# satshakit-M7.net
KiCad netlist of a schematic drawn in EAGLE
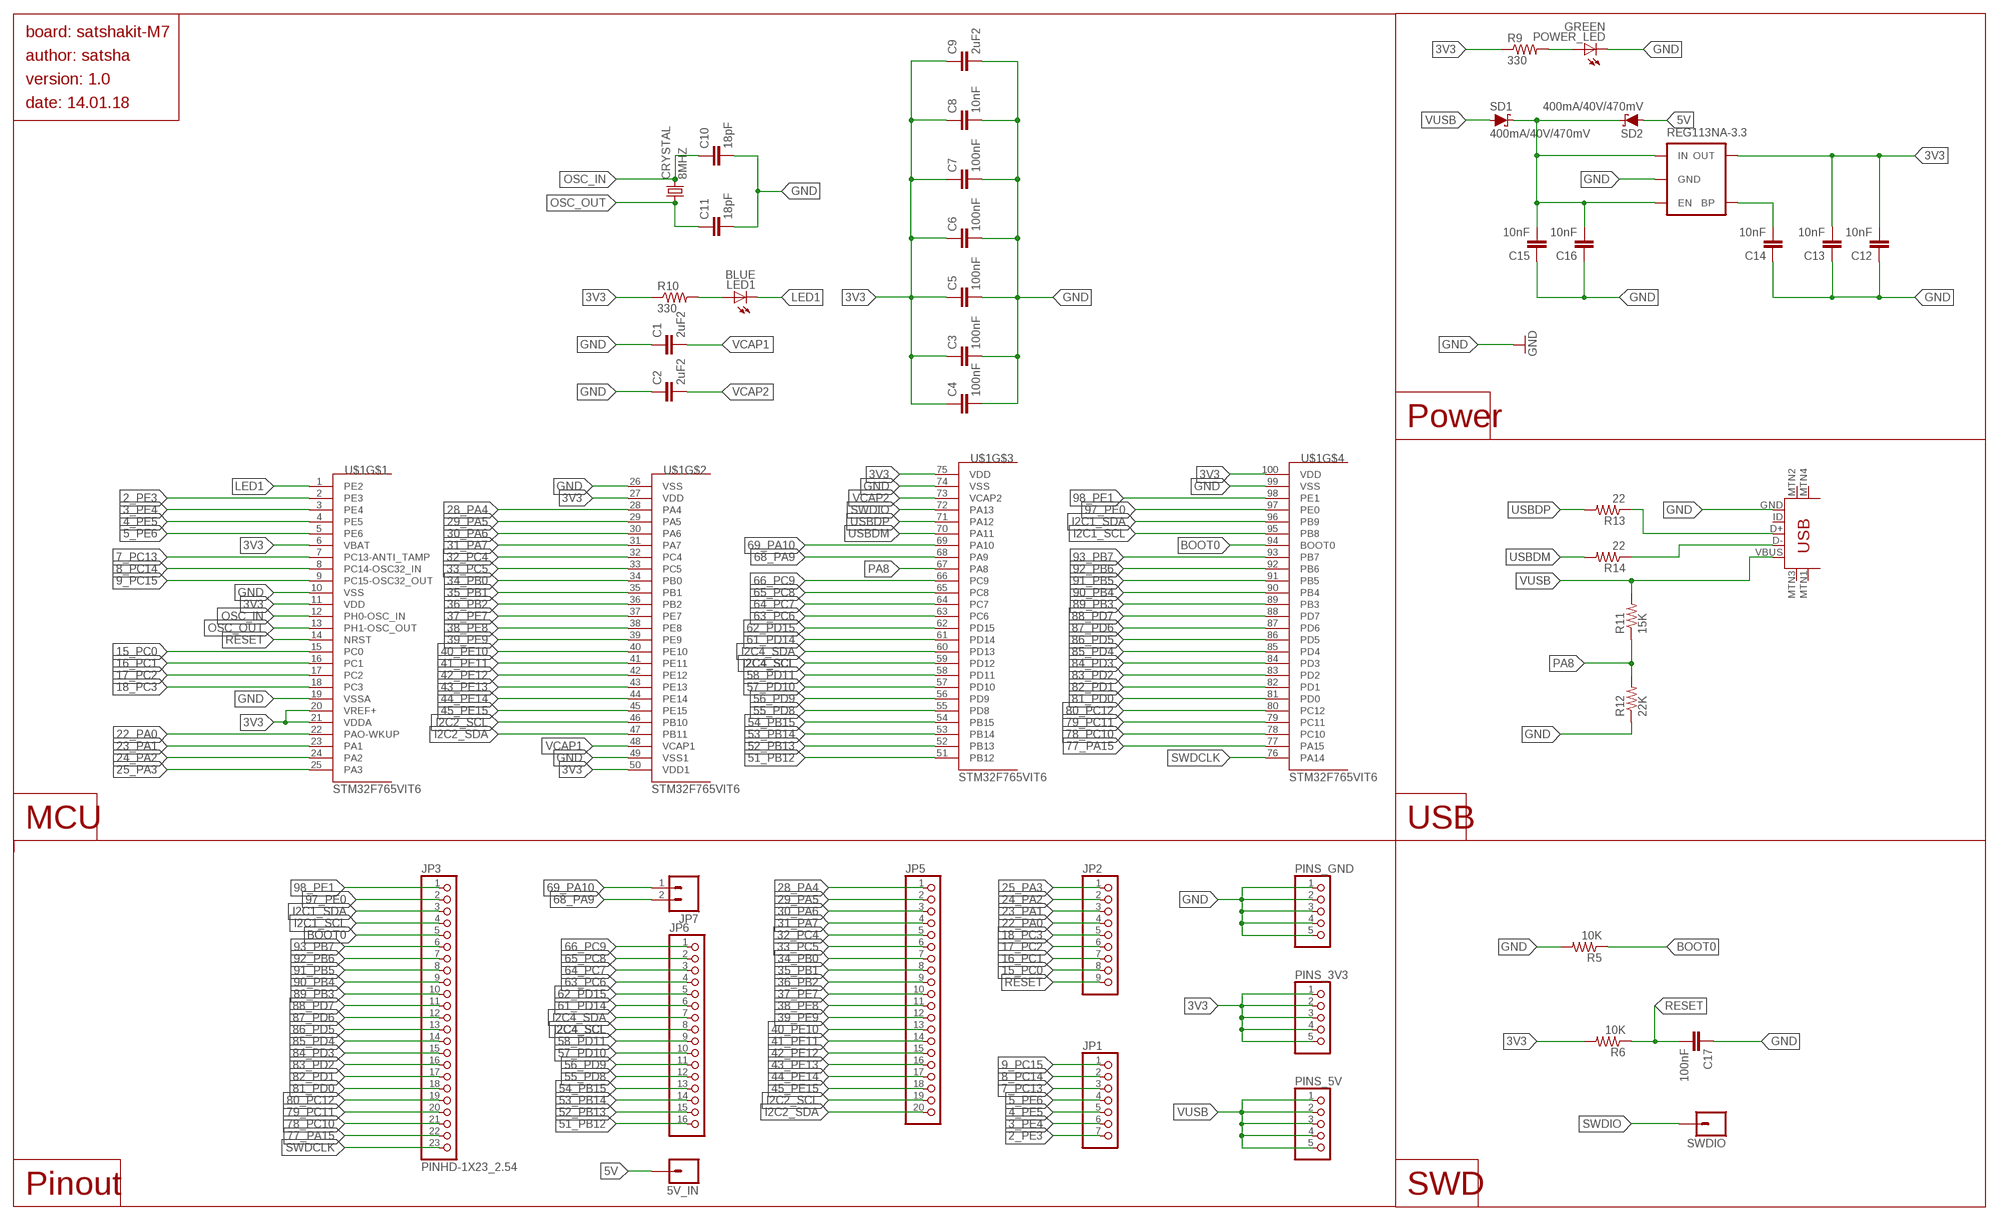
[diagram p0: schematic, sheet 1]

(export (version "E")
  (design (tool "Eeschema 10.0.6"))
  (components
    (comp (ref "5V_IN")
      (value "M01PTH_LONGPAD")
      (footprint "eagle-import:1X01_LONGPAD")
      (libsource (lib "eagle-import") (part "M01PTH_LONGPAD"))
    )
    (comp (ref "C1")
      (value "2uF2")
      (footprint "eagle-import:1206")
      (libsource (lib "eagle-import") (part "CAP1206"))
    )
    (comp (ref "C2")
      (value "2uF2")
      (footprint "eagle-import:1206")
      (libsource (lib "eagle-import") (part "CAP1206"))
    )
    (comp (ref "C3")
      (value "100nF")
      (footprint "eagle-import:1206")
      (libsource (lib "eagle-import") (part "CAP1206"))
    )
    (comp (ref "C4")
      (value "100nF")
      (footprint "eagle-import:1206")
      (libsource (lib "eagle-import") (part "CAP1206"))
    )
    (comp (ref "C5")
      (value "100nF")
      (footprint "eagle-import:1206")
      (libsource (lib "eagle-import") (part "CAP1206"))
    )
    (comp (ref "C6")
      (value "100nF")
      (footprint "eagle-import:1206")
      (libsource (lib "eagle-import") (part "CAP1206"))
    )
    (comp (ref "C7")
      (value "100nF")
      (footprint "eagle-import:1206")
      (libsource (lib "eagle-import") (part "CAP1206"))
    )
    (comp (ref "C8")
      (value "10nF")
      (footprint "eagle-import:1206")
      (libsource (lib "eagle-import") (part "CAP1206"))
    )
    (comp (ref "C9")
      (value "2uF2")
      (footprint "eagle-import:1206")
      (libsource (lib "eagle-import") (part "CAP1206"))
    )
    (comp (ref "C10")
      (value "18pF")
      (footprint "eagle-import:1206")
      (libsource (lib "eagle-import") (part "CAP1206"))
    )
    (comp (ref "C11")
      (value "18pF")
      (footprint "eagle-import:1206")
      (libsource (lib "eagle-import") (part "CAP1206"))
    )
    (comp (ref "C12")
      (value "10nF")
      (footprint "eagle-import:1206")
      (libsource (lib "eagle-import") (part "CAP1206"))
    )
    (comp (ref "C13")
      (value "10nF")
      (footprint "eagle-import:1206")
      (libsource (lib "eagle-import") (part "CAP1206"))
    )
    (comp (ref "C14")
      (value "10nF")
      (footprint "eagle-import:1206")
      (libsource (lib "eagle-import") (part "CAP1206"))
    )
    (comp (ref "C15")
      (value "10nF")
      (footprint "eagle-import:1206")
      (libsource (lib "eagle-import") (part "CAP1206"))
    )
    (comp (ref "C16")
      (value "10nF")
      (footprint "eagle-import:1206")
      (libsource (lib "eagle-import") (part "CAP1206"))
    )
    (comp (ref "C17")
      (value "100nF")
      (footprint "eagle-import:1206")
      (libsource (lib "eagle-import") (part "CAP1206"))
    )
    (comp (ref "CRYSTAL")
      (value "8MHZ")
      (footprint "eagle-import:CSM-7X-DU")
      (libsource (lib "eagle-import") (part "CSM-7X-DU"))
    )
    (comp (ref "JP1")
      (value "PINHD-1X07_2.54")
      (footprint "eagle-import:1X07")
      (libsource (lib "eagle-import") (part "PINHD-1X07_2.54"))
    )
    (comp (ref "JP2")
      (value "PINHD-1X09_2.54")
      (footprint "eagle-import:1X09")
      (libsource (lib "eagle-import") (part "PINHD-1X09_2.54"))
    )
    (comp (ref "JP3")
      (value "PINHD-1X23_2.54")
      (footprint "eagle-import:1X23")
      (libsource (lib "eagle-import") (part "PINHD-1X23_2.54"))
    )
    (comp (ref "JP5")
      (value "PINHD-1X20_2.54")
      (footprint "eagle-import:1X20")
      (libsource (lib "eagle-import") (part "PINHD-1X20_2.54"))
    )
    (comp (ref "JP6")
      (value "PINHD-1X16_2.54")
      (footprint "eagle-import:1X16")
      (libsource (lib "eagle-import") (part "PINHD-1X16_2.54"))
    )
    (comp (ref "JP7")
      (value "M02")
      (footprint "eagle-import:1X02_LONGPADS")
      (libsource (lib "eagle-import") (part "M02"))
    )
    (comp (ref "LED1")
      (value "BLUE")
      (footprint "eagle-import:1206")
      (libsource (lib "eagle-import") (part "LED1206"))
    )
    (comp (ref "PINS_3V3")
      (value "PINHD-1X05_2.54")
      (footprint "eagle-import:1X05")
      (libsource (lib "eagle-import") (part "PINHD-1X05_2.54"))
    )
    (comp (ref "PINS_5V")
      (value "PINHD-1X05_2.54")
      (footprint "eagle-import:1X05")
      (libsource (lib "eagle-import") (part "PINHD-1X05_2.54"))
    )
    (comp (ref "PINS_GND")
      (value "PINHD-1X05_2.54")
      (footprint "eagle-import:1X05")
      (libsource (lib "eagle-import") (part "PINHD-1X05_2.54"))
    )
    (comp (ref "POWER_LED")
      (value "GREEN")
      (footprint "eagle-import:1206")
      (libsource (lib "eagle-import") (part "LED1206"))
    )
    (comp (ref "R5")
      (value "10K")
      (footprint "eagle-import:1206")
      (libsource (lib "eagle-import") (part "RESISTOR1206"))
    )
    (comp (ref "R6")
      (value "10K")
      (footprint "eagle-import:1206")
      (libsource (lib "eagle-import") (part "RESISTOR1206"))
    )
    (comp (ref "R9")
      (value "330")
      (footprint "eagle-import:1206")
      (libsource (lib "eagle-import") (part "RESISTOR1206"))
    )
    (comp (ref "R10")
      (value "330")
      (footprint "eagle-import:1206")
      (libsource (lib "eagle-import") (part "RESISTOR1206"))
    )
    (comp (ref "R11")
      (value "15K")
      (footprint "eagle-import:1206")
      (libsource (lib "eagle-import") (part "RESISTOR1206"))
    )
    (comp (ref "R12")
      (value "22K")
      (footprint "eagle-import:1206")
      (libsource (lib "eagle-import") (part "RESISTOR1206"))
    )
    (comp (ref "R13")
      (value "22")
      (footprint "eagle-import:1206")
      (libsource (lib "eagle-import") (part "RESISTOR1206"))
    )
    (comp (ref "R14")
      (value "22")
      (footprint "eagle-import:1206")
      (libsource (lib "eagle-import") (part "RESISTOR1206"))
    )
    (comp (ref "REG113NA-3.3")
      (value "V_REG_LDOSMD")
      (footprint "eagle-import:SOT23-5")
      (libsource (lib "eagle-import") (part "V_REG_LDOSMD"))
    )
    (comp (ref "SD1")
      (value "400mA/40V/470mV")
      (footprint "eagle-import:SOT23-3")
      (libsource (lib "eagle-import") (part "DIODE-SCHOTTKY-ZLLS500"))
    )
    (comp (ref "SD2")
      (value "400mA/40V/470mV")
      (footprint "eagle-import:SOT23-3")
      (libsource (lib "eagle-import") (part "DIODE-SCHOTTKY-ZLLS500"))
    )
    (comp (ref "SWDIO")
      (value "M01PTH_LONGPAD")
      (footprint "eagle-import:1X01_LONGPAD")
      (libsource (lib "eagle-import") (part "M01PTH_LONGPAD"))
    )
    (comp (ref "U$1")
      (value "STM32F765VIT6")
      (footprint "eagle-import:LQFP100")
      (libsource (lib "eagle-import") (part "STM32F765VIT6"))
    )
    (comp (ref "U$7")
      (value "USB-MINIB-5PIN")
      (footprint "eagle-import:USB-MINIB")
      (libsource (lib "eagle-import") (part "USB-MINIB-5PIN"))
    )
  )
  (nets
    (net (code "1") (name "2_PE3") (class "Default")
      (node (ref "JP1") (pin "7") (pinfunction "7_7") (pintype "passive"))
      (node (ref "U$1") (pin "2") (pinfunction "PE3_2") (pintype "bidirectional"))
    )
    (net (code "2") (name "3V3") (class "Default")
      (node (ref "C12") (pin "2") (pinfunction "2_2") (pintype "passive"))
      (node (ref "C13") (pin "2") (pinfunction "2_2") (pintype "passive"))
      (node (ref "C3") (pin "1") (pinfunction "1_1") (pintype "passive"))
      (node (ref "C4") (pin "1") (pinfunction "1_1") (pintype "passive"))
      (node (ref "C5") (pin "1") (pinfunction "1_1") (pintype "passive"))
      (node (ref "C6") (pin "1") (pinfunction "1_1") (pintype "passive"))
      (node (ref "C7") (pin "1") (pinfunction "1_1") (pintype "passive"))
      (node (ref "C8") (pin "1") (pinfunction "1_1") (pintype "passive"))
      (node (ref "C9") (pin "1") (pinfunction "1_1") (pintype "passive"))
      (node (ref "PINS_3V3") (pin "1") (pinfunction "1_1") (pintype "passive"))
      (node (ref "PINS_3V3") (pin "2") (pinfunction "2_2") (pintype "passive"))
      (node (ref "PINS_3V3") (pin "3") (pinfunction "3_3") (pintype "passive"))
      (node (ref "PINS_3V3") (pin "4") (pinfunction "4_4") (pintype "passive"))
      (node (ref "PINS_3V3") (pin "5") (pinfunction "5_5") (pintype "passive"))
      (node (ref "R10") (pin "1") (pinfunction "1_1") (pintype "passive"))
      (node (ref "R6") (pin "2") (pinfunction "2_2") (pintype "passive"))
      (node (ref "R9") (pin "1") (pinfunction "1_1") (pintype "passive"))
      (node (ref "REG113NA-3.3") (pin "5") (pinfunction "OUT_5") (pintype "passive"))
      (node (ref "U$1") (pin "100") (pinfunction "VDD_100") (pintype "bidirectional"))
      (node (ref "U$1") (pin "11") (pinfunction "VDD_11") (pintype "bidirectional"))
      (node (ref "U$1") (pin "20") (pinfunction "VREF+_20") (pintype "bidirectional"))
      (node (ref "U$1") (pin "21") (pinfunction "VDDA_21") (pintype "bidirectional"))
      (node (ref "U$1") (pin "27") (pinfunction "VDD_27") (pintype "bidirectional"))
      (node (ref "U$1") (pin "50") (pinfunction "VDD1_50") (pintype "bidirectional"))
      (node (ref "U$1") (pin "6") (pinfunction "VBAT_6") (pintype "bidirectional"))
      (node (ref "U$1") (pin "75") (pinfunction "VDD_75") (pintype "bidirectional"))
    )
    (net (code "3") (name "3_PE4") (class "Default")
      (node (ref "JP1") (pin "6") (pinfunction "6_6") (pintype "passive"))
      (node (ref "U$1") (pin "3") (pinfunction "PE4_3") (pintype "bidirectional"))
    )
    (net (code "4") (name "4_PE5") (class "Default")
      (node (ref "JP1") (pin "5") (pinfunction "5_5") (pintype "passive"))
      (node (ref "U$1") (pin "4") (pinfunction "PE5_4") (pintype "bidirectional"))
    )
    (net (code "5") (name "5V") (class "Default")
      (node (ref "5V_IN") (pin "1") (pinfunction "1_1") (pintype "passive"))
      (node (ref "SD2") (pin "1") (pinfunction "A_1") (pintype "passive"))
    )
    (net (code "6") (name "5_PE6") (class "Default")
      (node (ref "JP1") (pin "4") (pinfunction "4_4") (pintype "passive"))
      (node (ref "U$1") (pin "5") (pinfunction "PE6_5") (pintype "bidirectional"))
    )
    (net (code "7") (name "7_PC13") (class "Default")
      (node (ref "JP1") (pin "3") (pinfunction "3_3") (pintype "passive"))
      (node (ref "U$1") (pin "7") (pinfunction "PC13-ANTI_TAMP_7") (pintype "bidirectional"))
    )
    (net (code "8") (name "8_PC14") (class "Default")
      (node (ref "JP1") (pin "2") (pinfunction "2_2") (pintype "passive"))
      (node (ref "U$1") (pin "8") (pinfunction "PC14-OSC32_IN_8") (pintype "bidirectional"))
    )
    (net (code "9") (name "9_PC15") (class "Default")
      (node (ref "JP1") (pin "1") (pinfunction "1_1") (pintype "passive"))
      (node (ref "U$1") (pin "9") (pinfunction "PC15-OSC32_OUT_9") (pintype "bidirectional"))
    )
    (net (code "10") (name "15_PC0") (class "Default")
      (node (ref "JP2") (pin "8") (pinfunction "8_8") (pintype "passive"))
      (node (ref "U$1") (pin "15") (pinfunction "PC0_15") (pintype "bidirectional"))
    )
    (net (code "11") (name "16_PC1") (class "Default")
      (node (ref "JP2") (pin "7") (pinfunction "7_7") (pintype "passive"))
      (node (ref "U$1") (pin "16") (pinfunction "PC1_16") (pintype "bidirectional"))
    )
    (net (code "12") (name "17_PC2") (class "Default")
      (node (ref "JP2") (pin "6") (pinfunction "6_6") (pintype "passive"))
      (node (ref "U$1") (pin "17") (pinfunction "PC2_17") (pintype "bidirectional"))
    )
    (net (code "13") (name "18_PC3") (class "Default")
      (node (ref "JP2") (pin "5") (pinfunction "5_5") (pintype "passive"))
      (node (ref "U$1") (pin "18") (pinfunction "PC3_18") (pintype "bidirectional"))
    )
    (net (code "14") (name "22_PA0") (class "Default")
      (node (ref "JP2") (pin "4") (pinfunction "4_4") (pintype "passive"))
      (node (ref "U$1") (pin "22") (pinfunction "PAO-WKUP_22") (pintype "bidirectional"))
    )
    (net (code "15") (name "23_PA1") (class "Default")
      (node (ref "JP2") (pin "3") (pinfunction "3_3") (pintype "passive"))
      (node (ref "U$1") (pin "23") (pinfunction "PA1_23") (pintype "bidirectional"))
    )
    (net (code "16") (name "24_PA2") (class "Default")
      (node (ref "JP2") (pin "2") (pinfunction "2_2") (pintype "passive"))
      (node (ref "U$1") (pin "24") (pinfunction "PA2_24") (pintype "bidirectional"))
    )
    (net (code "17") (name "25_PA3") (class "Default")
      (node (ref "JP2") (pin "1") (pinfunction "1_1") (pintype "passive"))
      (node (ref "U$1") (pin "25") (pinfunction "PA3_25") (pintype "bidirectional"))
    )
    (net (code "18") (name "28_PA4") (class "Default")
      (node (ref "JP5") (pin "1") (pinfunction "1_1") (pintype "passive"))
      (node (ref "U$1") (pin "28") (pinfunction "PA4_28") (pintype "bidirectional"))
    )
    (net (code "19") (name "29_PA5") (class "Default")
      (node (ref "JP5") (pin "2") (pinfunction "2_2") (pintype "passive"))
      (node (ref "U$1") (pin "29") (pinfunction "PA5_29") (pintype "bidirectional"))
    )
    (net (code "20") (name "30_PA6") (class "Default")
      (node (ref "JP5") (pin "3") (pinfunction "3_3") (pintype "passive"))
      (node (ref "U$1") (pin "30") (pinfunction "PA6_30") (pintype "bidirectional"))
    )
    (net (code "21") (name "31_PA7") (class "Default")
      (node (ref "JP5") (pin "4") (pinfunction "4_4") (pintype "passive"))
      (node (ref "U$1") (pin "31") (pinfunction "PA7_31") (pintype "bidirectional"))
    )
    (net (code "22") (name "32_PC4") (class "Default")
      (node (ref "JP5") (pin "5") (pinfunction "5_5") (pintype "passive"))
      (node (ref "U$1") (pin "32") (pinfunction "PC4_32") (pintype "bidirectional"))
    )
    (net (code "23") (name "33_PC5") (class "Default")
      (node (ref "JP5") (pin "6") (pinfunction "6_6") (pintype "passive"))
      (node (ref "U$1") (pin "33") (pinfunction "PC5_33") (pintype "bidirectional"))
    )
    (net (code "24") (name "34_PB0") (class "Default")
      (node (ref "JP5") (pin "7") (pinfunction "7_7") (pintype "passive"))
      (node (ref "U$1") (pin "34") (pinfunction "PB0_34") (pintype "bidirectional"))
    )
    (net (code "25") (name "35_PB1") (class "Default")
      (node (ref "JP5") (pin "8") (pinfunction "8_8") (pintype "passive"))
      (node (ref "U$1") (pin "35") (pinfunction "PB1_35") (pintype "bidirectional"))
    )
    (net (code "26") (name "36_PB2") (class "Default")
      (node (ref "JP5") (pin "9") (pinfunction "9_9") (pintype "passive"))
      (node (ref "U$1") (pin "36") (pinfunction "PB2_36") (pintype "bidirectional"))
    )
    (net (code "27") (name "37_PE7") (class "Default")
      (node (ref "JP5") (pin "10") (pinfunction "10_10") (pintype "passive"))
      (node (ref "U$1") (pin "37") (pinfunction "PE7_37") (pintype "bidirectional"))
    )
    (net (code "28") (name "38_PE8") (class "Default")
      (node (ref "JP5") (pin "11") (pinfunction "11_11") (pintype "passive"))
      (node (ref "U$1") (pin "38") (pinfunction "PE8_38") (pintype "bidirectional"))
    )
    (net (code "29") (name "39_PE9") (class "Default")
      (node (ref "JP5") (pin "12") (pinfunction "12_12") (pintype "passive"))
      (node (ref "U$1") (pin "39") (pinfunction "PE9_39") (pintype "bidirectional"))
    )
    (net (code "30") (name "40_PE10") (class "Default")
      (node (ref "JP5") (pin "13") (pinfunction "13_13") (pintype "passive"))
      (node (ref "U$1") (pin "40") (pinfunction "PE10_40") (pintype "bidirectional"))
    )
    (net (code "31") (name "41_PE11") (class "Default")
      (node (ref "JP5") (pin "14") (pinfunction "14_14") (pintype "passive"))
      (node (ref "U$1") (pin "41") (pinfunction "PE11_41") (pintype "bidirectional"))
    )
    (net (code "32") (name "42_PE12") (class "Default")
      (node (ref "JP5") (pin "15") (pinfunction "15_15") (pintype "passive"))
      (node (ref "U$1") (pin "42") (pinfunction "PE12_42") (pintype "bidirectional"))
    )
    (net (code "33") (name "43_PE13") (class "Default")
      (node (ref "JP5") (pin "16") (pinfunction "16_16") (pintype "passive"))
      (node (ref "U$1") (pin "43") (pinfunction "PE13_43") (pintype "bidirectional"))
    )
    (net (code "34") (name "44_PE14") (class "Default")
      (node (ref "JP5") (pin "17") (pinfunction "17_17") (pintype "passive"))
      (node (ref "U$1") (pin "44") (pinfunction "PE14_44") (pintype "bidirectional"))
    )
    (net (code "35") (name "45_PE15") (class "Default")
      (node (ref "JP5") (pin "18") (pinfunction "18_18") (pintype "passive"))
      (node (ref "U$1") (pin "45") (pinfunction "PE15_45") (pintype "bidirectional"))
    )
    (net (code "36") (name "51_PB12") (class "Default")
      (node (ref "JP6") (pin "16") (pinfunction "16_16") (pintype "passive"))
      (node (ref "U$1") (pin "51") (pinfunction "PB12_51") (pintype "bidirectional"))
    )
    (net (code "37") (name "52_PB13") (class "Default")
      (node (ref "JP6") (pin "15") (pinfunction "15_15") (pintype "passive"))
      (node (ref "U$1") (pin "52") (pinfunction "PB13_52") (pintype "bidirectional"))
    )
    (net (code "38") (name "53_PB14") (class "Default")
      (node (ref "JP6") (pin "14") (pinfunction "14_14") (pintype "passive"))
      (node (ref "U$1") (pin "53") (pinfunction "PB14_53") (pintype "bidirectional"))
    )
    (net (code "39") (name "54_PB15") (class "Default")
      (node (ref "JP6") (pin "13") (pinfunction "13_13") (pintype "passive"))
      (node (ref "U$1") (pin "54") (pinfunction "PB15_54") (pintype "bidirectional"))
    )
    (net (code "40") (name "55_PD8") (class "Default")
      (node (ref "JP6") (pin "12") (pinfunction "12_12") (pintype "passive"))
      (node (ref "U$1") (pin "55") (pinfunction "PD8_55") (pintype "bidirectional"))
    )
    (net (code "41") (name "56_PD9") (class "Default")
      (node (ref "JP6") (pin "11") (pinfunction "11_11") (pintype "passive"))
      (node (ref "U$1") (pin "56") (pinfunction "PD9_56") (pintype "bidirectional"))
    )
    (net (code "42") (name "57_PD10") (class "Default")
      (node (ref "JP6") (pin "10") (pinfunction "10_10") (pintype "passive"))
      (node (ref "U$1") (pin "57") (pinfunction "PD10_57") (pintype "bidirectional"))
    )
    (net (code "43") (name "58_PD11") (class "Default")
      (node (ref "JP6") (pin "9") (pinfunction "9_9") (pintype "passive"))
      (node (ref "U$1") (pin "58") (pinfunction "PD11_58") (pintype "bidirectional"))
    )
    (net (code "44") (name "61_PD14") (class "Default")
      (node (ref "JP6") (pin "6") (pinfunction "6_6") (pintype "passive"))
      (node (ref "U$1") (pin "61") (pinfunction "PD14_61") (pintype "bidirectional"))
    )
    (net (code "45") (name "62_PD15") (class "Default")
      (node (ref "JP6") (pin "5") (pinfunction "5_5") (pintype "passive"))
      (node (ref "U$1") (pin "62") (pinfunction "PD15_62") (pintype "bidirectional"))
    )
    (net (code "46") (name "63_PC6") (class "Default")
      (node (ref "JP6") (pin "4") (pinfunction "4_4") (pintype "passive"))
      (node (ref "U$1") (pin "63") (pinfunction "PC6_63") (pintype "bidirectional"))
    )
    (net (code "47") (name "64_PC7") (class "Default")
      (node (ref "JP6") (pin "3") (pinfunction "3_3") (pintype "passive"))
      (node (ref "U$1") (pin "64") (pinfunction "PC7_64") (pintype "bidirectional"))
    )
    (net (code "48") (name "65_PC8") (class "Default")
      (node (ref "JP6") (pin "2") (pinfunction "2_2") (pintype "passive"))
      (node (ref "U$1") (pin "65") (pinfunction "PC8_65") (pintype "bidirectional"))
    )
    (net (code "49") (name "66_PC9") (class "Default")
      (node (ref "JP6") (pin "1") (pinfunction "1_1") (pintype "passive"))
      (node (ref "U$1") (pin "66") (pinfunction "PC9_66") (pintype "bidirectional"))
    )
    (net (code "50") (name "68_PA9") (class "Default")
      (node (ref "JP7") (pin "2") (pinfunction "2_2") (pintype "passive"))
      (node (ref "U$1") (pin "68") (pinfunction "PA9_68") (pintype "bidirectional"))
    )
    (net (code "51") (name "69_PA10") (class "Default")
      (node (ref "JP7") (pin "1") (pinfunction "1_1") (pintype "passive"))
      (node (ref "U$1") (pin "69") (pinfunction "PA10_69") (pintype "bidirectional"))
    )
    (net (code "52") (name "77_PA15") (class "Default")
      (node (ref "JP3") (pin "22") (pinfunction "22_22") (pintype "passive"))
      (node (ref "U$1") (pin "77") (pinfunction "PA15_77") (pintype "bidirectional"))
    )
    (net (code "53") (name "78_PC10") (class "Default")
      (node (ref "JP3") (pin "21") (pinfunction "21_21") (pintype "passive"))
      (node (ref "U$1") (pin "78") (pinfunction "PC10_78") (pintype "bidirectional"))
    )
    (net (code "54") (name "79_PC11") (class "Default")
      (node (ref "JP3") (pin "20") (pinfunction "20_20") (pintype "passive"))
      (node (ref "U$1") (pin "79") (pinfunction "PC11_79") (pintype "bidirectional"))
    )
    (net (code "55") (name "80_PC12") (class "Default")
      (node (ref "JP3") (pin "19") (pinfunction "19_19") (pintype "passive"))
      (node (ref "U$1") (pin "80") (pinfunction "PC12_80") (pintype "bidirectional"))
    )
    (net (code "56") (name "81_PD0") (class "Default")
      (node (ref "JP3") (pin "18") (pinfunction "18_18") (pintype "passive"))
      (node (ref "U$1") (pin "81") (pinfunction "PD0_81") (pintype "bidirectional"))
    )
    (net (code "57") (name "82_PD1") (class "Default")
      (node (ref "JP3") (pin "17") (pinfunction "17_17") (pintype "passive"))
      (node (ref "U$1") (pin "82") (pinfunction "PD1_82") (pintype "bidirectional"))
    )
    (net (code "58") (name "83_PD2") (class "Default")
      (node (ref "JP3") (pin "16") (pinfunction "16_16") (pintype "passive"))
      (node (ref "U$1") (pin "83") (pinfunction "PD2_83") (pintype "bidirectional"))
    )
    (net (code "59") (name "84_PD3") (class "Default")
      (node (ref "JP3") (pin "15") (pinfunction "15_15") (pintype "passive"))
      (node (ref "U$1") (pin "84") (pinfunction "PD3_84") (pintype "bidirectional"))
    )
    (net (code "60") (name "85_PD4") (class "Default")
      (node (ref "JP3") (pin "14") (pinfunction "14_14") (pintype "passive"))
      (node (ref "U$1") (pin "85") (pinfunction "PD4_85") (pintype "bidirectional"))
    )
    (net (code "61") (name "86_PD5") (class "Default")
      (node (ref "JP3") (pin "13") (pinfunction "13_13") (pintype "passive"))
      (node (ref "U$1") (pin "86") (pinfunction "PD5_86") (pintype "bidirectional"))
    )
    (net (code "62") (name "87_PD6") (class "Default")
      (node (ref "JP3") (pin "12") (pinfunction "12_12") (pintype "passive"))
      (node (ref "U$1") (pin "87") (pinfunction "PD6_87") (pintype "bidirectional"))
    )
    (net (code "63") (name "88_PD7") (class "Default")
      (node (ref "JP3") (pin "11") (pinfunction "11_11") (pintype "passive"))
      (node (ref "U$1") (pin "88") (pinfunction "PD7_88") (pintype "bidirectional"))
    )
    (net (code "64") (name "89_PB3") (class "Default")
      (node (ref "JP3") (pin "10") (pinfunction "10_10") (pintype "passive"))
      (node (ref "U$1") (pin "89") (pinfunction "PB3_89") (pintype "bidirectional"))
    )
    (net (code "65") (name "90_PB4") (class "Default")
      (node (ref "JP3") (pin "9") (pinfunction "9_9") (pintype "passive"))
      (node (ref "U$1") (pin "90") (pinfunction "PB4_90") (pintype "bidirectional"))
    )
    (net (code "66") (name "91_PB5") (class "Default")
      (node (ref "JP3") (pin "8") (pinfunction "8_8") (pintype "passive"))
      (node (ref "U$1") (pin "91") (pinfunction "PB5_91") (pintype "bidirectional"))
    )
    (net (code "67") (name "92_PB6") (class "Default")
      (node (ref "JP3") (pin "7") (pinfunction "7_7") (pintype "passive"))
      (node (ref "U$1") (pin "92") (pinfunction "PB6_92") (pintype "bidirectional"))
    )
    (net (code "68") (name "93_PB7") (class "Default")
      (node (ref "JP3") (pin "6") (pinfunction "6_6") (pintype "passive"))
      (node (ref "U$1") (pin "93") (pinfunction "PB7_93") (pintype "bidirectional"))
    )
    (net (code "69") (name "97_PE0") (class "Default")
      (node (ref "JP3") (pin "2") (pinfunction "2_2") (pintype "passive"))
      (node (ref "U$1") (pin "97") (pinfunction "PE0_97") (pintype "bidirectional"))
    )
    (net (code "70") (name "98_PE1") (class "Default")
      (node (ref "JP3") (pin "1") (pinfunction "1_1") (pintype "passive"))
      (node (ref "U$1") (pin "98") (pinfunction "PE1_98") (pintype "bidirectional"))
    )
    (net (code "71") (name "BOOT0") (class "Default")
      (node (ref "JP3") (pin "5") (pinfunction "5_5") (pintype "passive"))
      (node (ref "R5") (pin "1") (pinfunction "1_1") (pintype "passive"))
      (node (ref "U$1") (pin "94") (pinfunction "BOOT0_94") (pintype "bidirectional"))
    )
    (net (code "72") (name "GND") (class "Default")
      (node (ref "C1") (pin "1") (pinfunction "1_1") (pintype "passive"))
      (node (ref "C10") (pin "2") (pinfunction "2_2") (pintype "passive"))
      (node (ref "C11") (pin "2") (pinfunction "2_2") (pintype "passive"))
      (node (ref "C12") (pin "1") (pinfunction "1_1") (pintype "passive"))
      (node (ref "C13") (pin "1") (pinfunction "1_1") (pintype "passive"))
      (node (ref "C14") (pin "1") (pinfunction "1_1") (pintype "passive"))
      (node (ref "C15") (pin "1") (pinfunction "1_1") (pintype "passive"))
      (node (ref "C16") (pin "1") (pinfunction "1_1") (pintype "passive"))
      (node (ref "C17") (pin "1") (pinfunction "1_1") (pintype "passive"))
      (node (ref "C2") (pin "1") (pinfunction "1_1") (pintype "passive"))
      (node (ref "C3") (pin "2") (pinfunction "2_2") (pintype "passive"))
      (node (ref "C4") (pin "2") (pinfunction "2_2") (pintype "passive"))
      (node (ref "C5") (pin "2") (pinfunction "2_2") (pintype "passive"))
      (node (ref "C6") (pin "2") (pinfunction "2_2") (pintype "passive"))
      (node (ref "C7") (pin "2") (pinfunction "2_2") (pintype "passive"))
      (node (ref "C8") (pin "2") (pinfunction "2_2") (pintype "passive"))
      (node (ref "C9") (pin "2") (pinfunction "2_2") (pintype "passive"))
      (node (ref "PINS_GND") (pin "1") (pinfunction "1_1") (pintype "passive"))
      (node (ref "PINS_GND") (pin "2") (pinfunction "2_2") (pintype "passive"))
      (node (ref "PINS_GND") (pin "3") (pinfunction "3_3") (pintype "passive"))
      (node (ref "PINS_GND") (pin "4") (pinfunction "4_4") (pintype "passive"))
      (node (ref "PINS_GND") (pin "5") (pinfunction "5_5") (pintype "passive"))
      (node (ref "POWER_LED") (pin "2") (pinfunction "C_2") (pintype "passive"))
      (node (ref "R12") (pin "1") (pinfunction "1_1") (pintype "passive"))
      (node (ref "R5") (pin "2") (pinfunction "2_2") (pintype "passive"))
      (node (ref "REG113NA-3.3") (pin "2") (pinfunction "GND_2") (pintype "input"))
      (node (ref "U$1") (pin "10") (pinfunction "VSS_10") (pintype "bidirectional"))
      (node (ref "U$1") (pin "19") (pinfunction "VSSA_19") (pintype "bidirectional"))
      (node (ref "U$1") (pin "26") (pinfunction "VSS_26") (pintype "bidirectional"))
      (node (ref "U$1") (pin "49") (pinfunction "VSS1_49") (pintype "bidirectional"))
      (node (ref "U$1") (pin "74") (pinfunction "VSS_74") (pintype "bidirectional"))
      (node (ref "U$1") (pin "99") (pinfunction "VSS_99") (pintype "bidirectional"))
      (node (ref "U$7") (pin "GND") (pinfunction "GND_GND") (pintype "bidirectional"))
    )
    (net (code "73") (name "I2C1_SCL") (class "Default")
      (node (ref "JP3") (pin "4") (pinfunction "4_4") (pintype "passive"))
      (node (ref "U$1") (pin "95") (pinfunction "PB8_95") (pintype "bidirectional"))
    )
    (net (code "74") (name "I2C1_SDA") (class "Default")
      (node (ref "JP3") (pin "3") (pinfunction "3_3") (pintype "passive"))
      (node (ref "U$1") (pin "96") (pinfunction "PB9_96") (pintype "bidirectional"))
    )
    (net (code "75") (name "I2C2_SCL") (class "Default")
      (node (ref "JP5") (pin "19") (pinfunction "19_19") (pintype "passive"))
      (node (ref "U$1") (pin "46") (pinfunction "PB10_46") (pintype "bidirectional"))
    )
    (net (code "76") (name "I2C2_SDA") (class "Default")
      (node (ref "JP5") (pin "20") (pinfunction "20_20") (pintype "passive"))
      (node (ref "U$1") (pin "47") (pinfunction "PB11_47") (pintype "bidirectional"))
    )
    (net (code "77") (name "I2C4_SCL") (class "Default")
      (node (ref "JP6") (pin "8") (pinfunction "8_8") (pintype "passive"))
      (node (ref "U$1") (pin "59") (pinfunction "PD12_59") (pintype "bidirectional"))
    )
    (net (code "78") (name "I2C4_SDA") (class "Default")
      (node (ref "JP6") (pin "7") (pinfunction "7_7") (pintype "passive"))
      (node (ref "U$1") (pin "60") (pinfunction "PD13_60") (pintype "bidirectional"))
    )
    (net (code "79") (name "LED1") (class "Default")
      (node (ref "LED1") (pin "2") (pinfunction "C_2") (pintype "passive"))
      (node (ref "U$1") (pin "1") (pinfunction "PE2_1") (pintype "bidirectional"))
    )
    (net (code "80") (name "Net-(LED1-A)") (class "Default")
      (node (ref "LED1") (pin "1") (pinfunction "A_1") (pintype "passive"))
      (node (ref "R10") (pin "2") (pinfunction "2_2") (pintype "passive"))
    )
    (net (code "81") (name "Net-(POWER_LED-A)") (class "Default")
      (node (ref "POWER_LED") (pin "1") (pinfunction "A_1") (pintype "passive"))
      (node (ref "R9") (pin "2") (pinfunction "2_2") (pintype "passive"))
    )
    (net (code "82") (name "Net-(R13-Pad1)") (class "Default")
      (node (ref "R13") (pin "1") (pinfunction "1_1") (pintype "passive"))
      (node (ref "U$7") (pin "D+") (pinfunction "D+_D+") (pintype "bidirectional"))
    )
    (net (code "83") (name "Net-(R14-Pad1)") (class "Default")
      (node (ref "R14") (pin "1") (pinfunction "1_1") (pintype "passive"))
      (node (ref "U$7") (pin "D-") (pinfunction "D-_D-") (pintype "bidirectional"))
    )
    (net (code "84") (name "Net-(REG113NA-3.3-BP)") (class "Default")
      (node (ref "C14") (pin "2") (pinfunction "2_2") (pintype "passive"))
      (node (ref "REG113NA-3.3") (pin "4") (pinfunction "BP_4") (pintype "input"))
    )
    (net (code "85") (name "Net-(REG113NA-3.3-EN)") (class "Default")
      (node (ref "C15") (pin "2") (pinfunction "2_2") (pintype "passive"))
      (node (ref "C16") (pin "2") (pinfunction "2_2") (pintype "passive"))
      (node (ref "REG113NA-3.3") (pin "1") (pinfunction "IN_1") (pintype "input"))
      (node (ref "REG113NA-3.3") (pin "3") (pinfunction "EN_3") (pintype "input"))
      (node (ref "SD1") (pin "3") (pinfunction "C_3") (pintype "passive"))
      (node (ref "SD2") (pin "3") (pinfunction "C_3") (pintype "passive"))
    )
    (net (code "86") (name "OSC_IN") (class "Default")
      (node (ref "C10") (pin "1") (pinfunction "1_1") (pintype "passive"))
      (node (ref "CRYSTAL") (pin "2") (pinfunction "2_2") (pintype "passive"))
      (node (ref "U$1") (pin "12") (pinfunction "PH0-OSC_IN_12") (pintype "bidirectional"))
    )
    (net (code "87") (name "OSC_OUT") (class "Default")
      (node (ref "C11") (pin "1") (pinfunction "1_1") (pintype "passive"))
      (node (ref "CRYSTAL") (pin "1") (pinfunction "1_1") (pintype "passive"))
      (node (ref "U$1") (pin "13") (pinfunction "PH1-OSC_OUT_13") (pintype "bidirectional"))
    )
    (net (code "88") (name "PA8") (class "Default")
      (node (ref "R11") (pin "1") (pinfunction "1_1") (pintype "passive"))
      (node (ref "R12") (pin "2") (pinfunction "2_2") (pintype "passive"))
      (node (ref "U$1") (pin "67") (pinfunction "PA8_67") (pintype "bidirectional"))
    )
    (net (code "89") (name "RESET") (class "Default")
      (node (ref "C17") (pin "2") (pinfunction "2_2") (pintype "passive"))
      (node (ref "JP2") (pin "9") (pinfunction "9_9") (pintype "passive"))
      (node (ref "R6") (pin "1") (pinfunction "1_1") (pintype "passive"))
      (node (ref "U$1") (pin "14") (pinfunction "NRST_14") (pintype "bidirectional"))
    )
    (net (code "90") (name "SWDCLK") (class "Default")
      (node (ref "JP3") (pin "23") (pinfunction "23_23") (pintype "passive"))
      (node (ref "U$1") (pin "76") (pinfunction "PA14_76") (pintype "bidirectional"))
    )
    (net (code "91") (name "SWDIO") (class "Default")
      (node (ref "SWDIO") (pin "1") (pinfunction "1_1") (pintype "passive"))
      (node (ref "U$1") (pin "72") (pinfunction "PA13_72") (pintype "bidirectional"))
    )
    (net (code "92") (name "USBDM") (class "Default")
      (node (ref "R14") (pin "2") (pinfunction "2_2") (pintype "passive"))
      (node (ref "U$1") (pin "70") (pinfunction "PA11_70") (pintype "bidirectional"))
    )
    (net (code "93") (name "USBDP") (class "Default")
      (node (ref "R13") (pin "2") (pinfunction "2_2") (pintype "passive"))
      (node (ref "U$1") (pin "71") (pinfunction "PA12_71") (pintype "bidirectional"))
    )
    (net (code "94") (name "VCAP1") (class "Default")
      (node (ref "C1") (pin "2") (pinfunction "2_2") (pintype "passive"))
      (node (ref "U$1") (pin "48") (pinfunction "VCAP1_48") (pintype "bidirectional"))
    )
    (net (code "95") (name "VCAP2") (class "Default")
      (node (ref "C2") (pin "2") (pinfunction "2_2") (pintype "passive"))
      (node (ref "U$1") (pin "73") (pinfunction "VCAP2_73") (pintype "bidirectional"))
    )
    (net (code "96") (name "VUSB") (class "Default")
      (node (ref "PINS_5V") (pin "1") (pinfunction "1_1") (pintype "passive"))
      (node (ref "PINS_5V") (pin "2") (pinfunction "2_2") (pintype "passive"))
      (node (ref "PINS_5V") (pin "3") (pinfunction "3_3") (pintype "passive"))
      (node (ref "PINS_5V") (pin "4") (pinfunction "4_4") (pintype "passive"))
      (node (ref "PINS_5V") (pin "5") (pinfunction "5_5") (pintype "passive"))
      (node (ref "R11") (pin "2") (pinfunction "2_2") (pintype "passive"))
      (node (ref "SD1") (pin "1") (pinfunction "A_1") (pintype "passive"))
      (node (ref "U$7") (pin "VBUS") (pinfunction "VBUS_VBUS") (pintype "bidirectional"))
    )
    (net (code "97") (name "unconnected-(U$7-MTN1-PadMTN3)") (class "Default")
      (node (ref "U$7") (pin "MTN3") (pinfunction "MTN1_MTN3") (pintype "bidirectional"))
    )
    (net (code "98") (name "unconnected-(U$7-MTN2-PadMTN1)") (class "Default")
      (node (ref "U$7") (pin "MTN1") (pinfunction "MTN2_MTN1") (pintype "bidirectional"))
    )
    (net (code "99") (name "unconnected-(U$7-MTN3-PadMTN2)") (class "Default")
      (node (ref "U$7") (pin "MTN2") (pinfunction "MTN3_MTN2") (pintype "bidirectional"))
    )
    (net (code "100") (name "unconnected-(U$7-PadID)") (class "Default")
      (node (ref "U$7") (pin "ID") (pinfunction "ID_ID") (pintype "bidirectional"))
    )
    (net (code "101") (name "unconnected-(U$7-PadMTN4)") (class "Default")
      (node (ref "U$7") (pin "MTN4") (pinfunction "MTN4_MTN4") (pintype "bidirectional"))
    )
  )
)
